# REVERSE_PROTECTION.net
KiCad netlist of a schematic drawn in Altium Designer
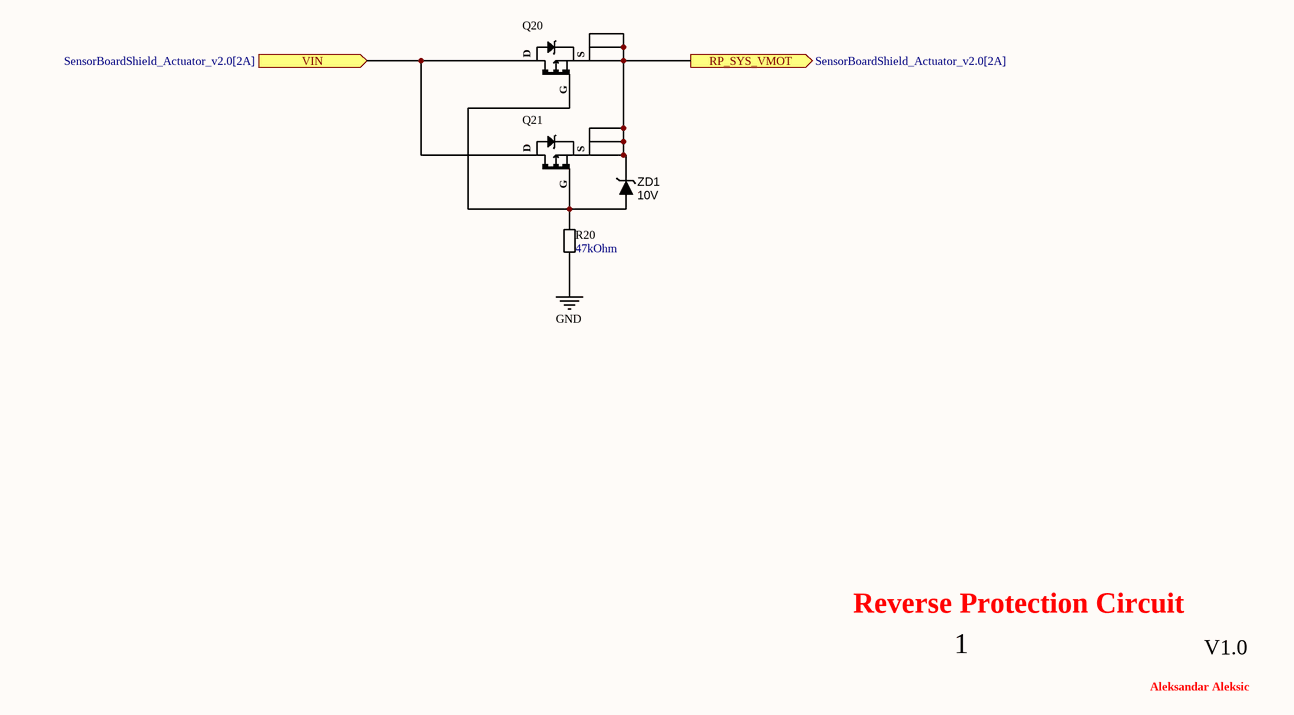
[diagram p0: REVERSE_PROTECTION.SchDoc]

(export (version "E")
  (design (tool "Eeschema 10.0.6"))
  (components
    (comp (ref "Q20")
      (value "SQJ659EP PMOS")
      (footprint "Miscellaneous_Lib1:PowerPAK SO-8L SINGLE")
      (description "P-Channel 60 V 52A (Tc) 83W (Tc) Surface Mount PowerPAK® SO-8")
      (fields
        (field (name "DIGIKEY PART NUMBER") "SQJ459EP-T1_GE3CT-ND")
        (field (name "MOUSER PART NUMBER") "78-SQJ459EP-T2_BE3")
      )
      (libsource (lib "Miscellaneous_Lib1") (part "00000005"))
    )
    (comp (ref "Q21")
      (value "SQJ659EP PMOS")
      (footprint "Miscellaneous_Lib1:PowerPAK SO-8L SINGLE")
      (description "P-Channel 60 V 52A (Tc) 83W (Tc) Surface Mount PowerPAK® SO-8")
      (fields
        (field (name "DIGIKEY PART NUMBER") "SQJ459EP-T1_GE3CT-ND")
        (field (name "MOUSER PART NUMBER") "78-SQJ459EP-T2_BE3")
      )
      (libsource (lib "Miscellaneous_Lib1") (part "00000005"))
    )
    (comp (ref "R20")
      (value "47kOhm")
      (footprint "RES_0603")
      (description "47 kOhms ±1% 0.1W, 1/10W Chip Resistor 0603 (1608 Metric) Moisture Resistant Thick Film")
      (fields (field (name "DIGIKEY PART NUMBER") "311-47.0KHRCT-ND"))
      (libsource (lib "ResistorsIntegrated") (part "R000010"))
    )
    (comp (ref "ZD1")
      (value "10V")
      (footprint "DIO_SMA")
      (description "Zener Diode 10 V 5 W ±5% Surface Mount SMC (DO-214AB)")
      (libsource (lib "IntegratedCircuits") (part "1SMA5931-AU_R1"))
    )
  )
  (nets
    (net (code "1") (name "/RP_SYS_VMOT") (class "Default")
      (node (ref "Q20") (pin "S") (pinfunction "S1_S") (pintype "passive"))
      (node (ref "Q21") (pin "S") (pinfunction "S1_S") (pintype "passive"))
      (node (ref "ZD1") (pin "1") (pinfunction "Cathode_1") (pintype "passive"))
    )
    (net (code "2") (name "/VIN") (class "Default")
      (node (ref "Q20") (pin "D") (pinfunction "D_D") (pintype "passive"))
      (node (ref "Q21") (pin "D") (pinfunction "D_D") (pintype "passive"))
    )
    (net (code "3") (name "GND") (class "Default")
      (node (ref "R20") (pin "1") (pinfunction "1_1") (pintype "passive"))
    )
    (net (code "4") (name "Net-(ZD1-Anode)") (class "Default")
      (node (ref "Q20") (pin "G") (pinfunction "G_G") (pintype "passive"))
      (node (ref "Q21") (pin "G") (pinfunction "G_G") (pintype "passive"))
      (node (ref "R20") (pin "2") (pinfunction "2_2") (pintype "passive"))
      (node (ref "ZD1") (pin "2") (pinfunction "Anode_2") (pintype "passive"))
    )
  )
)
